# MC_5V_3V_LDO.net
KiCad netlist of a schematic drawn in Altium Designer
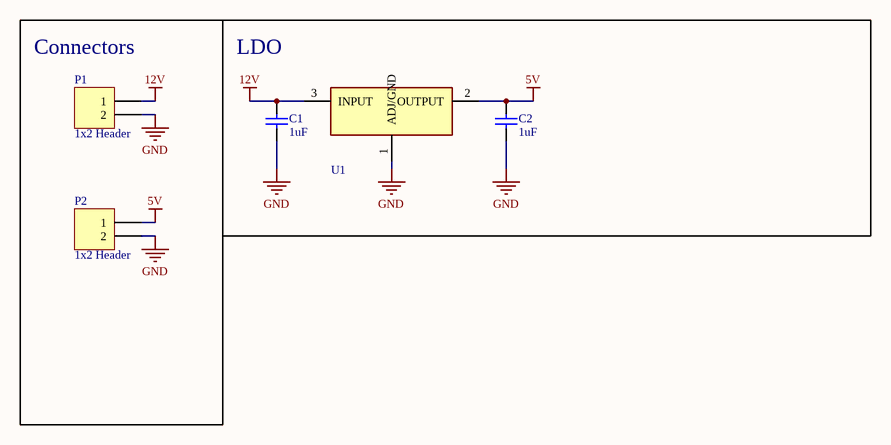
[diagram p0: MC_5V_3V_LDO.SchDoc]

(export (version "E")
  (design (tool "Eeschema 10.0.6"))
  (components
    (comp (ref "C1")
      (value "1uF")
      (footprint "0805 - Capacitor")
      (description "Nonpolarized Capacitor")
      (fields (field (name "Comment") "Capacitor - Nonpolarized"))
      (libsource (lib "General") (part "Capacitor - Nonpolarized"))
    )
    (comp (ref "C2")
      (value "1uF")
      (footprint "0805 - Capacitor")
      (description "Nonpolarized Capacitor")
      (fields (field (name "Comment") "Capacitor - Nonpolarized"))
      (libsource (lib "General") (part "Capacitor - Nonpolarized"))
    )
    (comp (ref "P1")
      (value "1x2 Header")
      (footprint "HDR1X2")
      (description "1x2 Pin Header")
      (libsource (lib "GeneralConnectors") (part "1x2 Header"))
    )
    (comp (ref "P2")
      (value "1x2 Header")
      (footprint "HDR1X2")
      (description "1x2 Pin Header")
      (libsource (lib "GeneralConnectors") (part "1x2 Header"))
    )
    (comp (ref "U1")
      (value "TLV1117-50IDCYR")
      (footprint "TLV1117")
      (description "Linear Voltage Regulator IC 5V 800MA SOT223-4")
      (fields (field (name "MANUFACTURER") "Texas Instruments"))
      (libsource (lib "GeneralComponents") (part "TLV1117-50IDCYR"))
    )
  )
  (nets
    (net (code "1") (name "5V") (class "Default")
      (node (ref "C2") (pin "2") (pinfunction "2_2") (pintype "passive"))
      (node (ref "P2") (pin "1") (pinfunction "1_1") (pintype "passive"))
      (node (ref "U1") (pin "2") (pinfunction "OUTPUT_2") (pintype "passive"))
    )
    (net (code "2") (name "12V") (class "Default")
      (node (ref "C1") (pin "2") (pinfunction "2_2") (pintype "passive"))
      (node (ref "P1") (pin "1") (pinfunction "1_1") (pintype "passive"))
      (node (ref "U1") (pin "3") (pinfunction "INPUT_3") (pintype "passive"))
    )
    (net (code "3") (name "GND") (class "Default")
      (node (ref "C1") (pin "1") (pinfunction "1_1") (pintype "passive"))
      (node (ref "C2") (pin "1") (pinfunction "1_1") (pintype "passive"))
      (node (ref "P1") (pin "2") (pinfunction "2_2") (pintype "passive"))
      (node (ref "P2") (pin "2") (pinfunction "2_2") (pintype "passive"))
      (node (ref "U1") (pin "1") (pinfunction "ADJ/GND_1") (pintype "passive"))
    )
  )
)
